# pck100clone.net
KiCad netlist of a schematic drawn in EAGLE
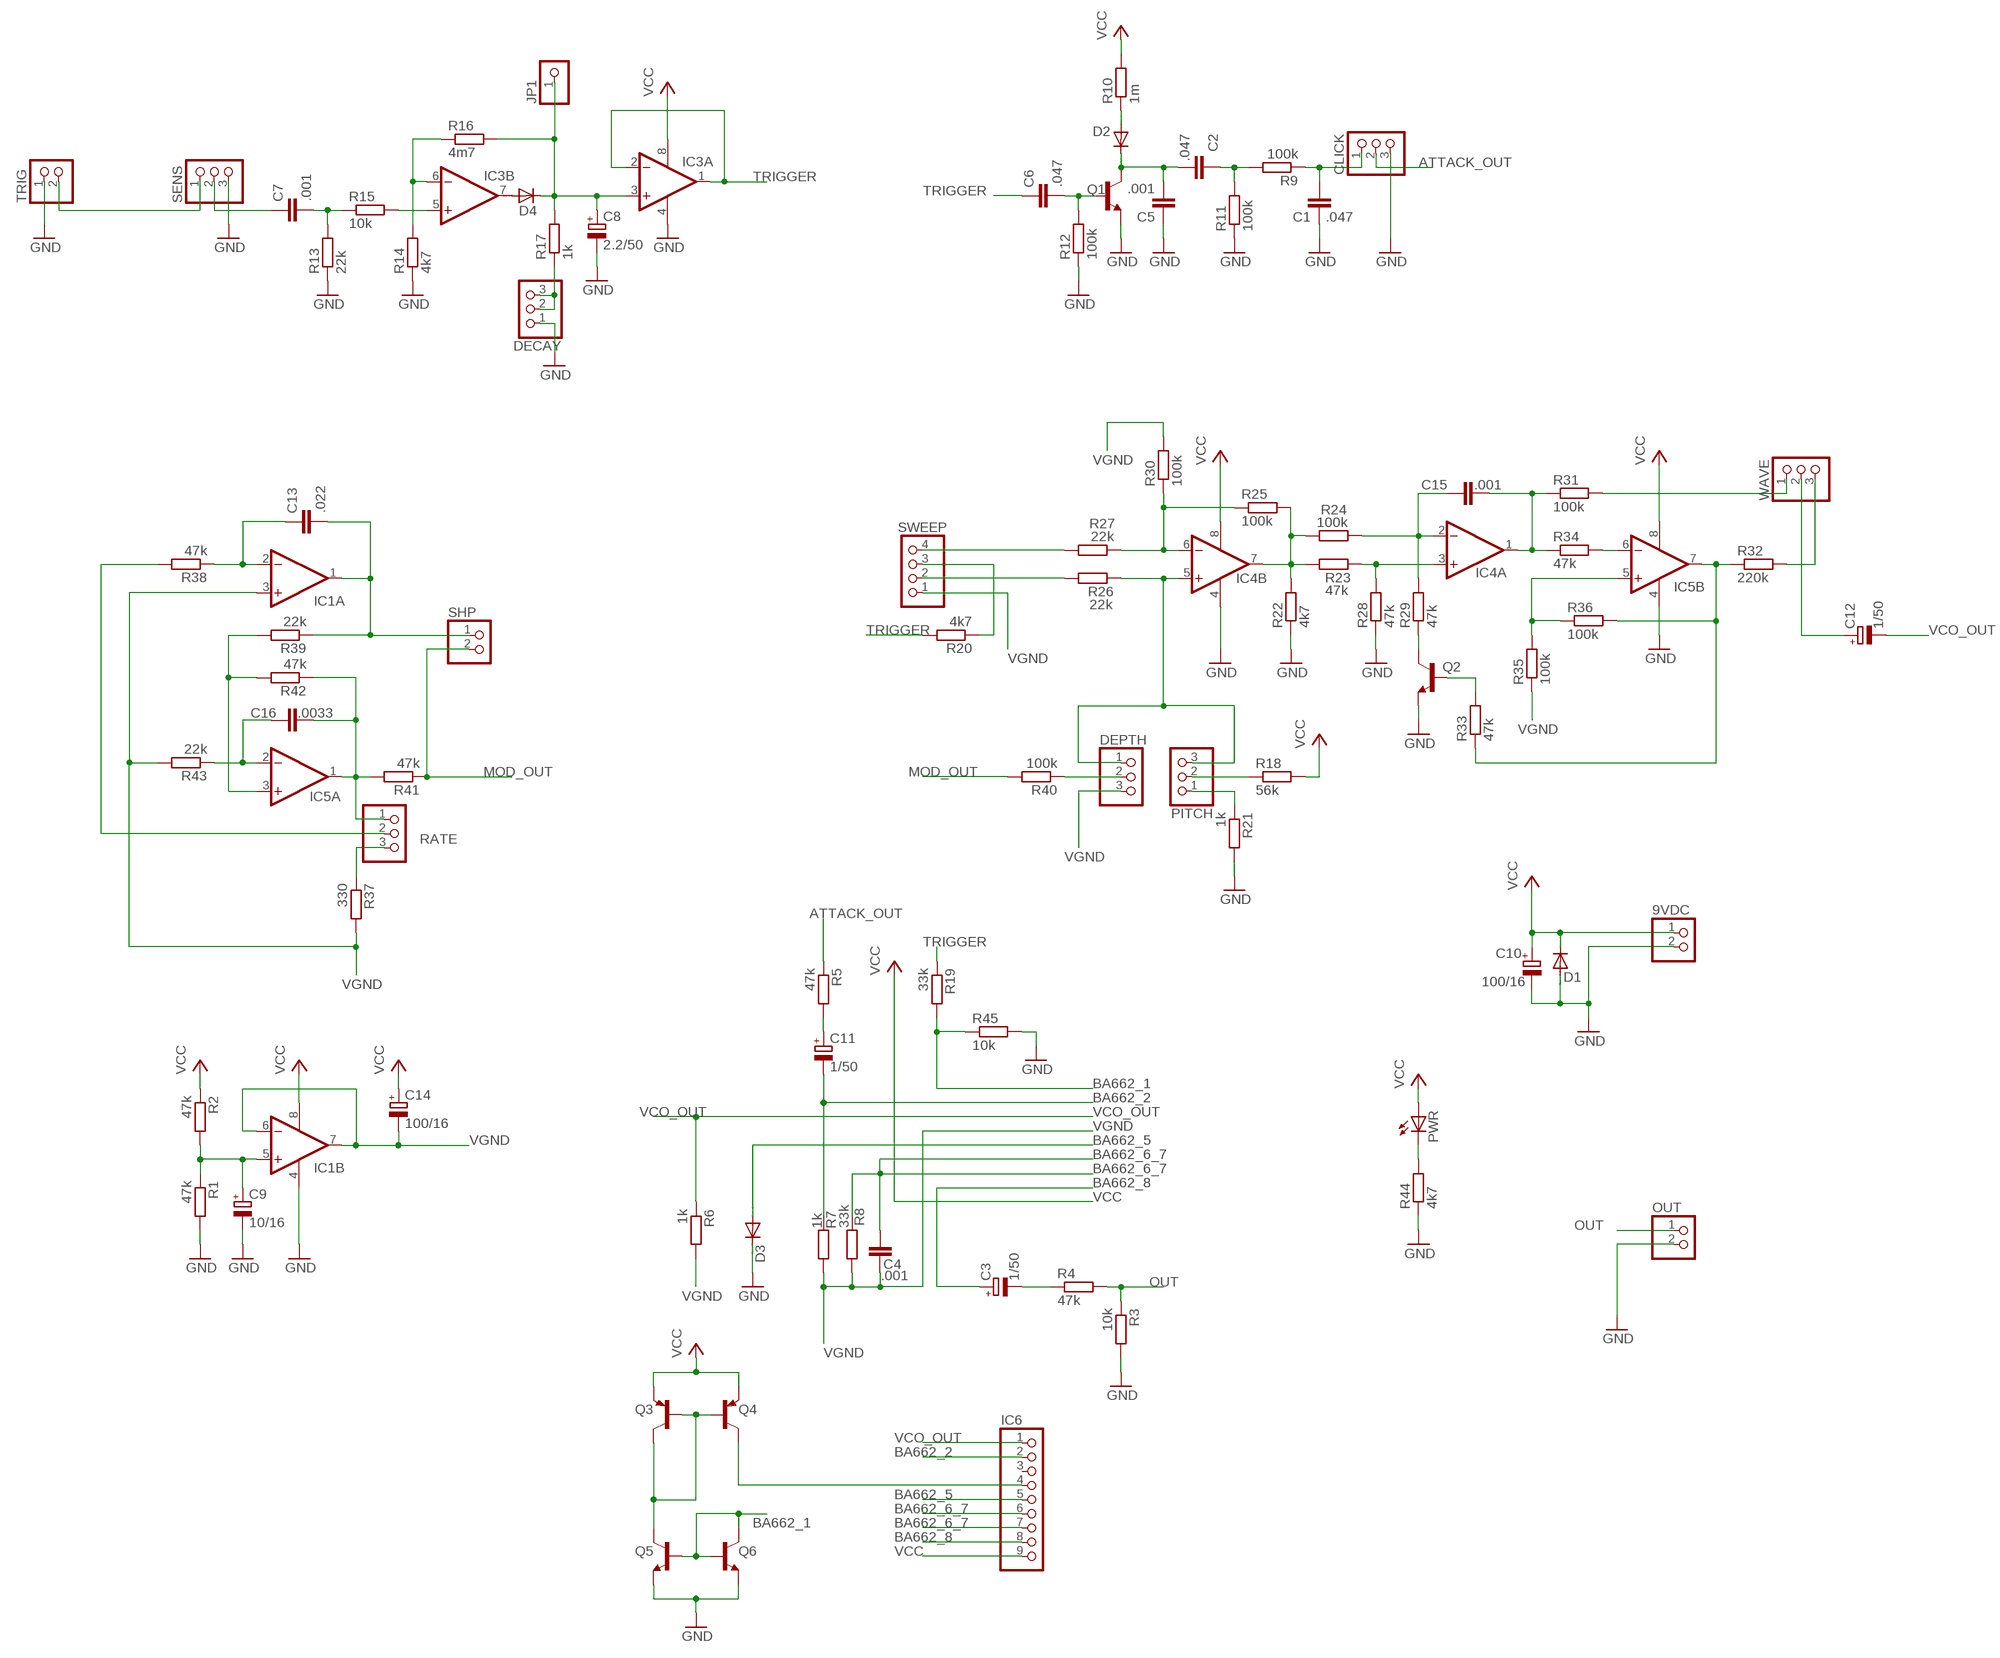
[diagram p0: schematic, sheet 1]

(export (version "E")
  (design (tool "Eeschema 10.0.6"))
  (components
    (comp (ref "9VDC")
      (value "PINHD-1X2")
      (footprint "eagle-import:1X02")
      (libsource (lib "eagle-import") (part "PINHD-1X2"))
    )
    (comp (ref "C1")
      (value ".047")
      (footprint "eagle-import:C050-025X075")
      (libsource (lib "eagle-import") (part "C-EU050-025X075"))
    )
    (comp (ref "C2")
      (value ".047")
      (footprint "eagle-import:C050-025X075")
      (libsource (lib "eagle-import") (part "C-EU050-025X075"))
    )
    (comp (ref "C3")
      (value "1/50")
      (footprint "eagle-import:E2,5-5")
      (libsource (lib "eagle-import") (part "CPOL-EUE2.5-5"))
    )
    (comp (ref "C4")
      (value ".001")
      (footprint "eagle-import:C050-025X075")
      (libsource (lib "eagle-import") (part "C-EU050-025X075"))
    )
    (comp (ref "C5")
      (value ".001")
      (footprint "eagle-import:C050-025X075")
      (libsource (lib "eagle-import") (part "C-EU050-025X075"))
    )
    (comp (ref "C6")
      (value ".047")
      (footprint "eagle-import:C050-025X075")
      (libsource (lib "eagle-import") (part "C-EU050-025X075"))
    )
    (comp (ref "C7")
      (value ".001")
      (footprint "eagle-import:C050-025X075")
      (libsource (lib "eagle-import") (part "C-EU050-025X075"))
    )
    (comp (ref "C8")
      (value "2.2/50")
      (footprint "eagle-import:E2,5-5")
      (libsource (lib "eagle-import") (part "CPOL-EUE2.5-5"))
    )
    (comp (ref "C9")
      (value "10/16")
      (footprint "eagle-import:E2,5-5")
      (libsource (lib "eagle-import") (part "CPOL-EUE2.5-5"))
    )
    (comp (ref "C10")
      (value "100/16")
      (footprint "eagle-import:E2,5-5")
      (libsource (lib "eagle-import") (part "CPOL-EUE2.5-5"))
    )
    (comp (ref "C11")
      (value "1/50")
      (footprint "eagle-import:E2,5-5")
      (libsource (lib "eagle-import") (part "CPOL-EUE2.5-5"))
    )
    (comp (ref "C12")
      (value "1/50")
      (footprint "eagle-import:E2,5-5")
      (libsource (lib "eagle-import") (part "CPOL-EUE2.5-5"))
    )
    (comp (ref "C13")
      (value ".022")
      (footprint "eagle-import:C050-025X075")
      (libsource (lib "eagle-import") (part "C-EU050-025X075"))
    )
    (comp (ref "C14")
      (value "100/16")
      (footprint "eagle-import:E2,5-5")
      (libsource (lib "eagle-import") (part "CPOL-EUE2.5-5"))
    )
    (comp (ref "C15")
      (value ".001")
      (footprint "eagle-import:C050-025X075")
      (libsource (lib "eagle-import") (part "C-EU050-025X075"))
    )
    (comp (ref "C16")
      (value ".0033")
      (footprint "eagle-import:C050-025X075")
      (libsource (lib "eagle-import") (part "C-EU050-025X075"))
    )
    (comp (ref "CLICK")
      (value "PINHD-1X3")
      (footprint "eagle-import:1X03")
      (libsource (lib "eagle-import") (part "PINHD-1X3"))
    )
    (comp (ref "D1")
      (value "1N4004")
      (footprint "eagle-import:DO41-10")
      (libsource (lib "eagle-import") (part "1N4004"))
    )
    (comp (ref "D2")
      (value "1N4148DO35-7")
      (footprint "eagle-import:DO35-7")
      (libsource (lib "eagle-import") (part "1N4148DO35-7"))
    )
    (comp (ref "D3")
      (value "1N4148DO35-7")
      (footprint "eagle-import:DO35-7")
      (libsource (lib "eagle-import") (part "1N4148DO35-7"))
    )
    (comp (ref "D4")
      (value "1N4148DO35-7")
      (footprint "eagle-import:DO35-7")
      (libsource (lib "eagle-import") (part "1N4148DO35-7"))
    )
    (comp (ref "DECAY")
      (value "PINHD-1X3")
      (footprint "eagle-import:1X03")
      (libsource (lib "eagle-import") (part "PINHD-1X3"))
    )
    (comp (ref "DEPTH")
      (value "PINHD-1X3")
      (footprint "eagle-import:1X03")
      (libsource (lib "eagle-import") (part "PINHD-1X3"))
    )
    (comp (ref "IC1")
      (value "LM358N")
      (footprint "eagle-import:DIL08")
      (libsource (lib "eagle-import") (part "LM358N"))
    )
    (comp (ref "IC3")
      (value "LM358N")
      (footprint "eagle-import:DIL08")
      (libsource (lib "eagle-import") (part "LM358N"))
    )
    (comp (ref "IC4")
      (value "LM358N")
      (footprint "eagle-import:DIL08")
      (libsource (lib "eagle-import") (part "LM358N"))
    )
    (comp (ref "IC5")
      (value "LM358N")
      (footprint "eagle-import:DIL08")
      (libsource (lib "eagle-import") (part "LM358N"))
    )
    (comp (ref "IC6")
      (value "PINHD-1X9")
      (footprint "eagle-import:1X09")
      (libsource (lib "eagle-import") (part "PINHD-1X9"))
    )
    (comp (ref "JP1")
      (value "PINHD-1X1")
      (footprint "eagle-import:1X01")
      (libsource (lib "eagle-import") (part "PINHD-1X1"))
    )
    (comp (ref "OUT")
      (value "PINHD-1X2")
      (footprint "eagle-import:1X02")
      (libsource (lib "eagle-import") (part "PINHD-1X2"))
    )
    (comp (ref "PITCH")
      (value "PINHD-1X3")
      (footprint "eagle-import:1X03")
      (libsource (lib "eagle-import") (part "PINHD-1X3"))
    )
    (comp (ref "PWR")
      (value "LED3MM")
      (footprint "eagle-import:LED3MM")
      (libsource (lib "eagle-import") (part "LED3MM"))
    )
    (comp (ref "Q1")
      (value "2SC945")
      (footprint "eagle-import:TO92-ECB")
      (libsource (lib "eagle-import") (part "2SC945"))
    )
    (comp (ref "Q2")
      (value "2SC945")
      (footprint "eagle-import:TO92-ECB")
      (libsource (lib "eagle-import") (part "2SC945"))
    )
    (comp (ref "Q3")
      (value "2N3906")
      (footprint "eagle-import:TO92")
      (libsource (lib "eagle-import") (part "2N3906"))
    )
    (comp (ref "Q4")
      (value "2N3906")
      (footprint "eagle-import:TO92")
      (libsource (lib "eagle-import") (part "2N3906"))
    )
    (comp (ref "Q5")
      (value "2N3904")
      (footprint "eagle-import:TO92")
      (libsource (lib "eagle-import") (part "2N3904"))
    )
    (comp (ref "Q6")
      (value "2N3904")
      (footprint "eagle-import:TO92")
      (libsource (lib "eagle-import") (part "2N3904"))
    )
    (comp (ref "R1")
      (value "47k")
      (footprint "eagle-import:0207_7")
      (libsource (lib "eagle-import") (part "R-EU_0207/7"))
    )
    (comp (ref "R2")
      (value "47k")
      (footprint "eagle-import:0207_7")
      (libsource (lib "eagle-import") (part "R-EU_0207/7"))
    )
    (comp (ref "R3")
      (value "10k")
      (footprint "eagle-import:0207_7")
      (libsource (lib "eagle-import") (part "R-EU_0207/7"))
    )
    (comp (ref "R4")
      (value "47k")
      (footprint "eagle-import:0207_7")
      (libsource (lib "eagle-import") (part "R-EU_0207/7"))
    )
    (comp (ref "R5")
      (value "47k")
      (footprint "eagle-import:0207_7")
      (libsource (lib "eagle-import") (part "R-EU_0207/7"))
    )
    (comp (ref "R6")
      (value "1k")
      (footprint "eagle-import:0207_7")
      (libsource (lib "eagle-import") (part "R-EU_0207/7"))
    )
    (comp (ref "R7")
      (value "1k")
      (footprint "eagle-import:0207_7")
      (libsource (lib "eagle-import") (part "R-EU_0207/7"))
    )
    (comp (ref "R8")
      (value "33k")
      (footprint "eagle-import:0207_7")
      (libsource (lib "eagle-import") (part "R-EU_0207/7"))
    )
    (comp (ref "R9")
      (value "100k")
      (footprint "eagle-import:0207_7")
      (libsource (lib "eagle-import") (part "R-EU_0207/7"))
    )
    (comp (ref "R10")
      (value "1m")
      (footprint "eagle-import:0207_7")
      (libsource (lib "eagle-import") (part "R-EU_0207/7"))
    )
    (comp (ref "R11")
      (value "100k")
      (footprint "eagle-import:0207_7")
      (libsource (lib "eagle-import") (part "R-EU_0207/7"))
    )
    (comp (ref "R12")
      (value "100k")
      (footprint "eagle-import:0207_7")
      (libsource (lib "eagle-import") (part "R-EU_0207/7"))
    )
    (comp (ref "R13")
      (value "22k")
      (footprint "eagle-import:0207_7")
      (libsource (lib "eagle-import") (part "R-EU_0207/7"))
    )
    (comp (ref "R14")
      (value "4k7")
      (footprint "eagle-import:0207_7")
      (libsource (lib "eagle-import") (part "R-EU_0207/7"))
    )
    (comp (ref "R15")
      (value "10k")
      (footprint "eagle-import:0207_7")
      (libsource (lib "eagle-import") (part "R-EU_0207/7"))
    )
    (comp (ref "R16")
      (value "4m7")
      (footprint "eagle-import:0207_7")
      (libsource (lib "eagle-import") (part "R-EU_0207/7"))
    )
    (comp (ref "R17")
      (value "1k")
      (footprint "eagle-import:0207_7")
      (libsource (lib "eagle-import") (part "R-EU_0207/7"))
    )
    (comp (ref "R18")
      (value "56k")
      (footprint "eagle-import:0207_7")
      (libsource (lib "eagle-import") (part "R-EU_0207/7"))
    )
    (comp (ref "R19")
      (value "33k")
      (footprint "eagle-import:0207_7")
      (libsource (lib "eagle-import") (part "R-EU_0207/7"))
    )
    (comp (ref "R20")
      (value "4k7")
      (footprint "eagle-import:0207_7")
      (libsource (lib "eagle-import") (part "R-EU_0207/7"))
    )
    (comp (ref "R21")
      (value "1k")
      (footprint "eagle-import:0207_7")
      (libsource (lib "eagle-import") (part "R-EU_0207/7"))
    )
    (comp (ref "R22")
      (value "4k7")
      (footprint "eagle-import:0207_7")
      (libsource (lib "eagle-import") (part "R-EU_0207/7"))
    )
    (comp (ref "R23")
      (value "47k")
      (footprint "eagle-import:0207_7")
      (libsource (lib "eagle-import") (part "R-EU_0207/7"))
    )
    (comp (ref "R24")
      (value "100k")
      (footprint "eagle-import:0207_7")
      (libsource (lib "eagle-import") (part "R-EU_0207/7"))
    )
    (comp (ref "R25")
      (value "100k")
      (footprint "eagle-import:0207_7")
      (libsource (lib "eagle-import") (part "R-EU_0207/7"))
    )
    (comp (ref "R26")
      (value "22k")
      (footprint "eagle-import:0207_7")
      (libsource (lib "eagle-import") (part "R-EU_0207/7"))
    )
    (comp (ref "R27")
      (value "22k")
      (footprint "eagle-import:0207_7")
      (libsource (lib "eagle-import") (part "R-EU_0207/7"))
    )
    (comp (ref "R28")
      (value "47k")
      (footprint "eagle-import:0207_7")
      (libsource (lib "eagle-import") (part "R-EU_0207/7"))
    )
    (comp (ref "R29")
      (value "47k")
      (footprint "eagle-import:0207_7")
      (libsource (lib "eagle-import") (part "R-EU_0207/7"))
    )
    (comp (ref "R30")
      (value "100k")
      (footprint "eagle-import:0207_7")
      (libsource (lib "eagle-import") (part "R-EU_0207/7"))
    )
    (comp (ref "R31")
      (value "100k")
      (footprint "eagle-import:0207_7")
      (libsource (lib "eagle-import") (part "R-EU_0207/7"))
    )
    (comp (ref "R32")
      (value "220k")
      (footprint "eagle-import:0207_7")
      (libsource (lib "eagle-import") (part "R-EU_0207/7"))
    )
    (comp (ref "R33")
      (value "47k")
      (footprint "eagle-import:0207_7")
      (libsource (lib "eagle-import") (part "R-EU_0207/7"))
    )
    (comp (ref "R34")
      (value "47k")
      (footprint "eagle-import:0207_7")
      (libsource (lib "eagle-import") (part "R-EU_0207/7"))
    )
    (comp (ref "R35")
      (value "100k")
      (footprint "eagle-import:0207_7")
      (libsource (lib "eagle-import") (part "R-EU_0207/7"))
    )
    (comp (ref "R36")
      (value "100k")
      (footprint "eagle-import:0207_7")
      (libsource (lib "eagle-import") (part "R-EU_0207/7"))
    )
    (comp (ref "R37")
      (value "330")
      (footprint "eagle-import:0207_7")
      (libsource (lib "eagle-import") (part "R-EU_0207/7"))
    )
    (comp (ref "R38")
      (value "47k")
      (footprint "eagle-import:0207_7")
      (libsource (lib "eagle-import") (part "R-EU_0207/7"))
    )
    (comp (ref "R39")
      (value "22k")
      (footprint "eagle-import:0207_7")
      (libsource (lib "eagle-import") (part "R-EU_0207/7"))
    )
    (comp (ref "R40")
      (value "100k")
      (footprint "eagle-import:0207_7")
      (libsource (lib "eagle-import") (part "R-EU_0207/7"))
    )
    (comp (ref "R41")
      (value "47k")
      (footprint "eagle-import:0207_7")
      (libsource (lib "eagle-import") (part "R-EU_0207/7"))
    )
    (comp (ref "R42")
      (value "47k")
      (footprint "eagle-import:0207_7")
      (libsource (lib "eagle-import") (part "R-EU_0207/7"))
    )
    (comp (ref "R43")
      (value "22k")
      (footprint "eagle-import:0207_7")
      (libsource (lib "eagle-import") (part "R-EU_0207/7"))
    )
    (comp (ref "R44")
      (value "4k7")
      (footprint "eagle-import:0207_7")
      (libsource (lib "eagle-import") (part "R-EU_0207/7"))
    )
    (comp (ref "R45")
      (value "10k")
      (footprint "eagle-import:0207_7")
      (libsource (lib "eagle-import") (part "R-EU_0207/7"))
    )
    (comp (ref "RATE")
      (value "PINHD-1X3")
      (footprint "eagle-import:1X03")
      (libsource (lib "eagle-import") (part "PINHD-1X3"))
    )
    (comp (ref "SENS")
      (value "PINHD-1X3")
      (footprint "eagle-import:1X03")
      (libsource (lib "eagle-import") (part "PINHD-1X3"))
    )
    (comp (ref "SHP")
      (value "PINHD-1X2")
      (footprint "eagle-import:1X02")
      (libsource (lib "eagle-import") (part "PINHD-1X2"))
    )
    (comp (ref "SWEEP")
      (value "PINHD-1X4")
      (footprint "eagle-import:1X04")
      (libsource (lib "eagle-import") (part "PINHD-1X4"))
    )
    (comp (ref "TRIG")
      (value "PINHD-1X2")
      (footprint "eagle-import:1X02")
      (libsource (lib "eagle-import") (part "PINHD-1X2"))
    )
    (comp (ref "WAVE")
      (value "PINHD-1X3")
      (footprint "eagle-import:1X03")
      (libsource (lib "eagle-import") (part "PINHD-1X3"))
    )
  )
  (nets
    (net (code "1") (name "/ATTACK_OUT") (class "Default")
      (node (ref "CLICK") (pin "2") (pinfunction "2_2") (pintype "passive"))
      (node (ref "R5") (pin "1") (pinfunction "1_1") (pintype "passive"))
    )
    (net (code "2") (name "/BA662_1") (class "Default")
      (node (ref "Q5") (pin "2") (pinfunction "B_2") (pintype "passive"))
      (node (ref "Q6") (pin "1") (pinfunction "C_1") (pintype "passive"))
      (node (ref "Q6") (pin "2") (pinfunction "B_2") (pintype "passive"))
      (node (ref "R19") (pin "2") (pinfunction "2_2") (pintype "passive"))
      (node (ref "R45") (pin "1") (pinfunction "1_1") (pintype "passive"))
    )
    (net (code "3") (name "/BA662_2") (class "Default")
      (node (ref "C11") (pin "-") (pinfunction "-_-") (pintype "passive"))
      (node (ref "IC6") (pin "2") (pinfunction "2_2") (pintype "passive"))
      (node (ref "R7") (pin "1") (pinfunction "1_1") (pintype "passive"))
    )
    (net (code "4") (name "/BA662_5") (class "Default")
      (node (ref "D3") (pin "A") (pinfunction "A_A") (pintype "passive"))
      (node (ref "IC6") (pin "5") (pinfunction "5_5") (pintype "passive"))
    )
    (net (code "5") (name "/BA662_6_7") (class "Default")
      (node (ref "C4") (pin "2") (pinfunction "2_2") (pintype "passive"))
      (node (ref "IC6") (pin "6") (pinfunction "6_6") (pintype "passive"))
      (node (ref "IC6") (pin "7") (pinfunction "7_7") (pintype "passive"))
      (node (ref "R8") (pin "1") (pinfunction "1_1") (pintype "passive"))
    )
    (net (code "6") (name "/BA662_8") (class "Default")
      (node (ref "C3") (pin "+") (pinfunction "+_+") (pintype "passive"))
      (node (ref "IC6") (pin "8") (pinfunction "8_8") (pintype "passive"))
    )
    (net (code "7") (name "/MOD_OUT") (class "Default")
      (node (ref "R40") (pin "2") (pinfunction "2_2") (pintype "passive"))
      (node (ref "R41") (pin "1") (pinfunction "1_1") (pintype "passive"))
      (node (ref "SHP") (pin "2") (pinfunction "2_2") (pintype "passive"))
    )
    (net (code "8") (name "/OUT") (class "Default")
      (node (ref "OUT") (pin "1") (pinfunction "1_1") (pintype "passive"))
      (node (ref "R3") (pin "1") (pinfunction "1_1") (pintype "passive"))
      (node (ref "R4") (pin "2") (pinfunction "2_2") (pintype "passive"))
    )
    (net (code "9") (name "/TRIGGER") (class "Default")
      (node (ref "C6") (pin "1") (pinfunction "1_1") (pintype "passive"))
      (node (ref "IC3") (pin "1") (pinfunction "OUT_1") (pintype "output"))
      (node (ref "IC3") (pin "2") (pinfunction "-IN_2") (pintype "input"))
      (node (ref "R19") (pin "1") (pinfunction "1_1") (pintype "passive"))
      (node (ref "R20") (pin "2") (pinfunction "2_2") (pintype "passive"))
    )
    (net (code "10") (name "/VCO_OUT") (class "Default")
      (node (ref "C12") (pin "-") (pinfunction "-_-") (pintype "passive"))
      (node (ref "IC6") (pin "1") (pinfunction "1_1") (pintype "passive"))
      (node (ref "R6") (pin "1") (pinfunction "1_1") (pintype "passive"))
    )
    (net (code "11") (name "/VGND") (class "Default")
      (node (ref "C14") (pin "-") (pinfunction "-_-") (pintype "passive"))
      (node (ref "C4") (pin "1") (pinfunction "1_1") (pintype "passive"))
      (node (ref "DEPTH") (pin "3") (pinfunction "3_3") (pintype "passive"))
      (node (ref "IC1") (pin "3") (pinfunction "+IN_3") (pintype "input"))
      (node (ref "IC1") (pin "6") (pinfunction "-IN_6") (pintype "input"))
      (node (ref "IC1") (pin "7") (pinfunction "OUT_7") (pintype "output"))
      (node (ref "R30") (pin "2") (pinfunction "2_2") (pintype "passive"))
      (node (ref "R35") (pin "1") (pinfunction "1_1") (pintype "passive"))
      (node (ref "R37") (pin "2") (pinfunction "2_2") (pintype "passive"))
      (node (ref "R43") (pin "2") (pinfunction "2_2") (pintype "passive"))
      (node (ref "R6") (pin "2") (pinfunction "2_2") (pintype "passive"))
      (node (ref "R7") (pin "2") (pinfunction "2_2") (pintype "passive"))
      (node (ref "R8") (pin "2") (pinfunction "2_2") (pintype "passive"))
      (node (ref "SWEEP") (pin "1") (pinfunction "1_1") (pintype "passive"))
    )
    (net (code "12") (name "GND") (class "Default")
      (node (ref "9VDC") (pin "2") (pinfunction "2_2") (pintype "passive"))
      (node (ref "C1") (pin "1") (pinfunction "1_1") (pintype "passive"))
      (node (ref "C10") (pin "-") (pinfunction "-_-") (pintype "passive"))
      (node (ref "C5") (pin "1") (pinfunction "1_1") (pintype "passive"))
      (node (ref "C8") (pin "-") (pinfunction "-_-") (pintype "passive"))
      (node (ref "C9") (pin "-") (pinfunction "-_-") (pintype "passive"))
      (node (ref "CLICK") (pin "3") (pinfunction "3_3") (pintype "passive"))
      (node (ref "D1") (pin "A") (pinfunction "A_A") (pintype "passive"))
      (node (ref "D3") (pin "C") (pinfunction "C_C") (pintype "passive"))
      (node (ref "DECAY") (pin "1") (pinfunction "1_1") (pintype "passive"))
      (node (ref "IC1") (pin "4") (pinfunction "V-_4") (pintype "power_in"))
      (node (ref "IC3") (pin "4") (pinfunction "V-_4") (pintype "power_in"))
      (node (ref "IC4") (pin "4") (pinfunction "V-_4") (pintype "power_in"))
      (node (ref "IC5") (pin "4") (pinfunction "V-_4") (pintype "power_in"))
      (node (ref "OUT") (pin "2") (pinfunction "2_2") (pintype "passive"))
      (node (ref "Q1") (pin "E") (pinfunction "E_E") (pintype "passive"))
      (node (ref "Q2") (pin "E") (pinfunction "E_E") (pintype "passive"))
      (node (ref "Q5") (pin "3") (pinfunction "E_3") (pintype "passive"))
      (node (ref "Q6") (pin "3") (pinfunction "E_3") (pintype "passive"))
      (node (ref "R1") (pin "2") (pinfunction "2_2") (pintype "passive"))
      (node (ref "R11") (pin "1") (pinfunction "1_1") (pintype "passive"))
      (node (ref "R12") (pin "1") (pinfunction "1_1") (pintype "passive"))
      (node (ref "R13") (pin "1") (pinfunction "1_1") (pintype "passive"))
      (node (ref "R14") (pin "1") (pinfunction "1_1") (pintype "passive"))
      (node (ref "R21") (pin "2") (pinfunction "2_2") (pintype "passive"))
      (node (ref "R22") (pin "1") (pinfunction "1_1") (pintype "passive"))
      (node (ref "R28") (pin "1") (pinfunction "1_1") (pintype "passive"))
      (node (ref "R3") (pin "2") (pinfunction "2_2") (pintype "passive"))
      (node (ref "R44") (pin "1") (pinfunction "1_1") (pintype "passive"))
      (node (ref "R45") (pin "2") (pinfunction "2_2") (pintype "passive"))
      (node (ref "SENS") (pin "3") (pinfunction "3_3") (pintype "passive"))
      (node (ref "TRIG") (pin "1") (pinfunction "1_1") (pintype "passive"))
    )
    (net (code "13") (name "Net-(C1-Pad2)") (class "Default")
      (node (ref "C1") (pin "2") (pinfunction "2_2") (pintype "passive"))
      (node (ref "CLICK") (pin "1") (pinfunction "1_1") (pintype "passive"))
      (node (ref "R9") (pin "1") (pinfunction "1_1") (pintype "passive"))
    )
    (net (code "14") (name "Net-(C2-Pad1)") (class "Default")
      (node (ref "C2") (pin "1") (pinfunction "1_1") (pintype "passive"))
      (node (ref "R11") (pin "2") (pinfunction "2_2") (pintype "passive"))
      (node (ref "R9") (pin "2") (pinfunction "2_2") (pintype "passive"))
    )
    (net (code "15") (name "Net-(C2-Pad2)") (class "Default")
      (node (ref "C2") (pin "2") (pinfunction "2_2") (pintype "passive"))
      (node (ref "C5") (pin "2") (pinfunction "2_2") (pintype "passive"))
      (node (ref "D2") (pin "C") (pinfunction "C_C") (pintype "passive"))
      (node (ref "Q1") (pin "C") (pinfunction "C_C") (pintype "passive"))
    )
    (net (code "16") (name "Net-(C3-Pad-)") (class "Default")
      (node (ref "C3") (pin "-") (pinfunction "-_-") (pintype "passive"))
      (node (ref "R4") (pin "1") (pinfunction "1_1") (pintype "passive"))
    )
    (net (code "17") (name "Net-(C6-Pad2)") (class "Default")
      (node (ref "C6") (pin "2") (pinfunction "2_2") (pintype "passive"))
      (node (ref "Q1") (pin "B") (pinfunction "B_B") (pintype "passive"))
      (node (ref "R12") (pin "2") (pinfunction "2_2") (pintype "passive"))
    )
    (net (code "18") (name "Net-(C7-Pad1)") (class "Default")
      (node (ref "C7") (pin "1") (pinfunction "1_1") (pintype "passive"))
      (node (ref "SENS") (pin "2") (pinfunction "2_2") (pintype "passive"))
    )
    (net (code "19") (name "Net-(C7-Pad2)") (class "Default")
      (node (ref "C7") (pin "2") (pinfunction "2_2") (pintype "passive"))
      (node (ref "R13") (pin "2") (pinfunction "2_2") (pintype "passive"))
      (node (ref "R15") (pin "1") (pinfunction "1_1") (pintype "passive"))
    )
    (net (code "20") (name "Net-(C11-Pad+)") (class "Default")
      (node (ref "C11") (pin "+") (pinfunction "+_+") (pintype "passive"))
      (node (ref "R5") (pin "2") (pinfunction "2_2") (pintype "passive"))
    )
    (net (code "21") (name "Net-(C12-Pad+)") (class "Default")
      (node (ref "C12") (pin "+") (pinfunction "+_+") (pintype "passive"))
      (node (ref "WAVE") (pin "2") (pinfunction "2_2") (pintype "passive"))
    )
    (net (code "22") (name "Net-(D2-PadA)") (class "Default")
      (node (ref "D2") (pin "A") (pinfunction "A_A") (pintype "passive"))
      (node (ref "R10") (pin "1") (pinfunction "1_1") (pintype "passive"))
    )
    (net (code "23") (name "Net-(DECAY-Pad2)") (class "Default")
      (node (ref "DECAY") (pin "2") (pinfunction "2_2") (pintype "passive"))
      (node (ref "DECAY") (pin "3") (pinfunction "3_3") (pintype "passive"))
      (node (ref "R17") (pin "1") (pinfunction "1_1") (pintype "passive"))
    )
    (net (code "24") (name "Net-(DEPTH-Pad2)") (class "Default")
      (node (ref "DEPTH") (pin "2") (pinfunction "2_2") (pintype "passive"))
      (node (ref "R40") (pin "1") (pinfunction "1_1") (pintype "passive"))
    )
    (net (code "25") (name "Net-(IC1A--IN)") (class "Default")
      (node (ref "C13") (pin "1") (pinfunction "1_1") (pintype "passive"))
      (node (ref "IC1") (pin "2") (pinfunction "-IN_2") (pintype "input"))
      (node (ref "R38") (pin "1") (pinfunction "1_1") (pintype "passive"))
    )
    (net (code "26") (name "Net-(IC1A-OUT)") (class "Default")
      (node (ref "C13") (pin "2") (pinfunction "2_2") (pintype "passive"))
      (node (ref "IC1") (pin "1") (pinfunction "OUT_1") (pintype "output"))
      (node (ref "R39") (pin "1") (pinfunction "1_1") (pintype "passive"))
      (node (ref "SHP") (pin "1") (pinfunction "1_1") (pintype "passive"))
    )
    (net (code "27") (name "Net-(IC1B-+IN)") (class "Default")
      (node (ref "C9") (pin "+") (pinfunction "+_+") (pintype "passive"))
      (node (ref "IC1") (pin "5") (pinfunction "+IN_5") (pintype "input"))
      (node (ref "R1") (pin "1") (pinfunction "1_1") (pintype "passive"))
      (node (ref "R2") (pin "2") (pinfunction "2_2") (pintype "passive"))
    )
    (net (code "28") (name "Net-(IC3A-+IN)") (class "Default")
      (node (ref "C8") (pin "+") (pinfunction "+_+") (pintype "passive"))
      (node (ref "D4") (pin "C") (pinfunction "C_C") (pintype "passive"))
      (node (ref "IC3") (pin "3") (pinfunction "+IN_3") (pintype "input"))
      (node (ref "JP1") (pin "1") (pinfunction "1_1") (pintype "passive"))
      (node (ref "R16") (pin "2") (pinfunction "2_2") (pintype "passive"))
      (node (ref "R17") (pin "2") (pinfunction "2_2") (pintype "passive"))
    )
    (net (code "29") (name "Net-(IC3B-+IN)") (class "Default")
      (node (ref "IC3") (pin "5") (pinfunction "+IN_5") (pintype "input"))
      (node (ref "R15") (pin "2") (pinfunction "2_2") (pintype "passive"))
    )
    (net (code "30") (name "Net-(IC3B--IN)") (class "Default")
      (node (ref "IC3") (pin "6") (pinfunction "-IN_6") (pintype "input"))
      (node (ref "R14") (pin "2") (pinfunction "2_2") (pintype "passive"))
      (node (ref "R16") (pin "1") (pinfunction "1_1") (pintype "passive"))
    )
    (net (code "31") (name "Net-(IC3B-OUT)") (class "Default")
      (node (ref "D4") (pin "A") (pinfunction "A_A") (pintype "passive"))
      (node (ref "IC3") (pin "7") (pinfunction "OUT_7") (pintype "output"))
    )
    (net (code "32") (name "Net-(IC4A-+IN)") (class "Default")
      (node (ref "IC4") (pin "3") (pinfunction "+IN_3") (pintype "input"))
      (node (ref "R23") (pin "2") (pinfunction "2_2") (pintype "passive"))
      (node (ref "R28") (pin "2") (pinfunction "2_2") (pintype "passive"))
    )
    (net (code "33") (name "Net-(IC4A--IN)") (class "Default")
      (node (ref "C15") (pin "2") (pinfunction "2_2") (pintype "passive"))
      (node (ref "IC4") (pin "2") (pinfunction "-IN_2") (pintype "input"))
      (node (ref "R24") (pin "2") (pinfunction "2_2") (pintype "passive"))
      (node (ref "R29") (pin "2") (pinfunction "2_2") (pintype "passive"))
    )
    (net (code "34") (name "Net-(IC4A-OUT)") (class "Default")
      (node (ref "C15") (pin "1") (pinfunction "1_1") (pintype "passive"))
      (node (ref "IC4") (pin "1") (pinfunction "OUT_1") (pintype "output"))
      (node (ref "R31") (pin "1") (pinfunction "1_1") (pintype "passive"))
      (node (ref "R34") (pin "1") (pinfunction "1_1") (pintype "passive"))
    )
    (net (code "35") (name "Net-(IC4B-+IN)") (class "Default")
      (node (ref "DEPTH") (pin "1") (pinfunction "1_1") (pintype "passive"))
      (node (ref "IC4") (pin "5") (pinfunction "+IN_5") (pintype "input"))
      (node (ref "PITCH") (pin "3") (pinfunction "3_3") (pintype "passive"))
      (node (ref "R26") (pin "1") (pinfunction "1_1") (pintype "passive"))
    )
    (net (code "36") (name "Net-(IC4B--IN)") (class "Default")
      (node (ref "IC4") (pin "6") (pinfunction "-IN_6") (pintype "input"))
      (node (ref "R25") (pin "1") (pinfunction "1_1") (pintype "passive"))
      (node (ref "R27") (pin "1") (pinfunction "1_1") (pintype "passive"))
      (node (ref "R30") (pin "1") (pinfunction "1_1") (pintype "passive"))
    )
    (net (code "37") (name "Net-(IC4B-OUT)") (class "Default")
      (node (ref "IC4") (pin "7") (pinfunction "OUT_7") (pintype "output"))
      (node (ref "R22") (pin "2") (pinfunction "2_2") (pintype "passive"))
      (node (ref "R23") (pin "1") (pinfunction "1_1") (pintype "passive"))
      (node (ref "R24") (pin "1") (pinfunction "1_1") (pintype "passive"))
      (node (ref "R25") (pin "2") (pinfunction "2_2") (pintype "passive"))
    )
    (net (code "38") (name "Net-(IC5A-+IN)") (class "Default")
      (node (ref "IC5") (pin "3") (pinfunction "+IN_3") (pintype "input"))
      (node (ref "R39") (pin "2") (pinfunction "2_2") (pintype "passive"))
      (node (ref "R42") (pin "2") (pinfunction "2_2") (pintype "passive"))
    )
    (net (code "39") (name "Net-(IC5A--IN)") (class "Default")
      (node (ref "C16") (pin "1") (pinfunction "1_1") (pintype "passive"))
      (node (ref "IC5") (pin "2") (pinfunction "-IN_2") (pintype "input"))
      (node (ref "R43") (pin "1") (pinfunction "1_1") (pintype "passive"))
    )
    (net (code "40") (name "Net-(IC5A-OUT)") (class "Default")
      (node (ref "C16") (pin "2") (pinfunction "2_2") (pintype "passive"))
      (node (ref "IC5") (pin "1") (pinfunction "OUT_1") (pintype "output"))
      (node (ref "R41") (pin "2") (pinfunction "2_2") (pintype "passive"))
      (node (ref "R42") (pin "1") (pinfunction "1_1") (pintype "passive"))
      (node (ref "RATE") (pin "1") (pinfunction "1_1") (pintype "passive"))
    )
    (net (code "41") (name "Net-(IC5B-+IN)") (class "Default")
      (node (ref "IC5") (pin "5") (pinfunction "+IN_5") (pintype "input"))
      (node (ref "R35") (pin "2") (pinfunction "2_2") (pintype "passive"))
      (node (ref "R36") (pin "1") (pinfunction "1_1") (pintype "passive"))
    )
    (net (code "42") (name "Net-(IC5B--IN)") (class "Default")
      (node (ref "IC5") (pin "6") (pinfunction "-IN_6") (pintype "input"))
      (node (ref "R34") (pin "2") (pinfunction "2_2") (pintype "passive"))
    )
    (net (code "43") (name "Net-(IC5B-OUT)") (class "Default")
      (node (ref "IC5") (pin "7") (pinfunction "OUT_7") (pintype "output"))
      (node (ref "R32") (pin "1") (pinfunction "1_1") (pintype "passive"))
      (node (ref "R33") (pin "1") (pinfunction "1_1") (pintype "passive"))
      (node (ref "R36") (pin "2") (pinfunction "2_2") (pintype "passive"))
    )
    (net (code "44") (name "Net-(PITCH-Pad1)") (class "Default")
      (node (ref "PITCH") (pin "1") (pinfunction "1_1") (pintype "passive"))
      (node (ref "R21") (pin "1") (pinfunction "1_1") (pintype "passive"))
    )
    (net (code "45") (name "Net-(PITCH-Pad2)") (class "Default")
      (node (ref "PITCH") (pin "2") (pinfunction "2_2") (pintype "passive"))
      (node (ref "R18") (pin "1") (pinfunction "1_1") (pintype "passive"))
    )
    (net (code "46") (name "Net-(PWR-C)") (class "Default")
      (node (ref "PWR") (pin "K") (pinfunction "C_K") (pintype "passive"))
      (node (ref "R44") (pin "2") (pinfunction "2_2") (pintype "passive"))
    )
    (net (code "47") (name "Net-(Q2-PadB)") (class "Default")
      (node (ref "Q2") (pin "B") (pinfunction "B_B") (pintype "passive"))
      (node (ref "R33") (pin "2") (pinfunction "2_2") (pintype "passive"))
    )
    (net (code "48") (name "Net-(Q2-PadC)") (class "Default")
      (node (ref "Q2") (pin "C") (pinfunction "C_C") (pintype "passive"))
      (node (ref "R29") (pin "1") (pinfunction "1_1") (pintype "passive"))
    )
    (net (code "49") (name "Net-(Q3-B)") (class "Default")
      (node (ref "Q3") (pin "1") (pinfunction "C_1") (pintype "passive"))
      (node (ref "Q3") (pin "2") (pinfunction "B_2") (pintype "passive"))
      (node (ref "Q4") (pin "2") (pinfunction "B_2") (pintype "passive"))
      (node (ref "Q5") (pin "1") (pinfunction "C_1") (pintype "passive"))
    )
    (net (code "50") (name "Net-(Q4-C)") (class "Default")
      (node (ref "IC6") (pin "4") (pinfunction "4_4") (pintype "passive"))
      (node (ref "Q4") (pin "1") (pinfunction "C_1") (pintype "passive"))
    )
    (net (code "51") (name "Net-(R20-Pad1)") (class "Default")
      (node (ref "R20") (pin "1") (pinfunction "1_1") (pintype "passive"))
      (node (ref "SWEEP") (pin "3") (pinfunction "3_3") (pintype "passive"))
    )
    (net (code "52") (name "Net-(R26-Pad2)") (class "Default")
      (node (ref "R26") (pin "2") (pinfunction "2_2") (pintype "passive"))
      (node (ref "SWEEP") (pin "2") (pinfunction "2_2") (pintype "passive"))
    )
    (net (code "53") (name "Net-(R27-Pad2)") (class "Default")
      (node (ref "R27") (pin "2") (pinfunction "2_2") (pintype "passive"))
      (node (ref "SWEEP") (pin "4") (pinfunction "4_4") (pintype "passive"))
    )
    (net (code "54") (name "Net-(R31-Pad2)") (class "Default")
      (node (ref "R31") (pin "2") (pinfunction "2_2") (pintype "passive"))
      (node (ref "WAVE") (pin "1") (pinfunction "1_1") (pintype "passive"))
    )
    (net (code "55") (name "Net-(R32-Pad2)") (class "Default")
      (node (ref "R32") (pin "2") (pinfunction "2_2") (pintype "passive"))
      (node (ref "WAVE") (pin "3") (pinfunction "3_3") (pintype "passive"))
    )
    (net (code "56") (name "Net-(R37-Pad1)") (class "Default")
      (node (ref "R37") (pin "1") (pinfunction "1_1") (pintype "passive"))
      (node (ref "RATE") (pin "3") (pinfunction "3_3") (pintype "passive"))
    )
    (net (code "57") (name "Net-(R38-Pad2)") (class "Default")
      (node (ref "R38") (pin "2") (pinfunction "2_2") (pintype "passive"))
      (node (ref "RATE") (pin "2") (pinfunction "2_2") (pintype "passive"))
    )
    (net (code "58") (name "Net-(SENS-Pad1)") (class "Default")
      (node (ref "SENS") (pin "1") (pinfunction "1_1") (pintype "passive"))
      (node (ref "TRIG") (pin "2") (pinfunction "2_2") (pintype "passive"))
    )
    (net (code "59") (name "VCC") (class "Default")
      (node (ref "9VDC") (pin "1") (pinfunction "1_1") (pintype "passive"))
      (node (ref "C10") (pin "+") (pinfunction "+_+") (pintype "passive"))
      (node (ref "C14") (pin "+") (pinfunction "+_+") (pintype "passive"))
      (node (ref "D1") (pin "C") (pinfunction "C_C") (pintype "passive"))
      (node (ref "IC1") (pin "8") (pinfunction "V+_8") (pintype "power_in"))
      (node (ref "IC3") (pin "8") (pinfunction "V+_8") (pintype "power_in"))
      (node (ref "IC4") (pin "8") (pinfunction "V+_8") (pintype "power_in"))
      (node (ref "IC5") (pin "8") (pinfunction "V+_8") (pintype "power_in"))
      (node (ref "IC6") (pin "9") (pinfunction "9_9") (pintype "passive"))
      (node (ref "PWR") (pin "A") (pinfunction "A_A") (pintype "passive"))
      (node (ref "Q3") (pin "3") (pinfunction "E_3") (pintype "passive"))
      (node (ref "Q4") (pin "3") (pinfunction "E_3") (pintype "passive"))
      (node (ref "R10") (pin "2") (pinfunction "2_2") (pintype "passive"))
      (node (ref "R18") (pin "2") (pinfunction "2_2") (pintype "passive"))
      (node (ref "R2") (pin "1") (pinfunction "1_1") (pintype "passive"))
    )
    (net (code "60") (name "unconnected-(IC6-Pad3)") (class "Default")
      (node (ref "IC6") (pin "3") (pinfunction "3_3") (pintype "passive"))
    )
  )
)
